# Load_Bank_Mosfet_Control_Board_rev2.net
KiCad netlist of a schematic drawn in EAGLE
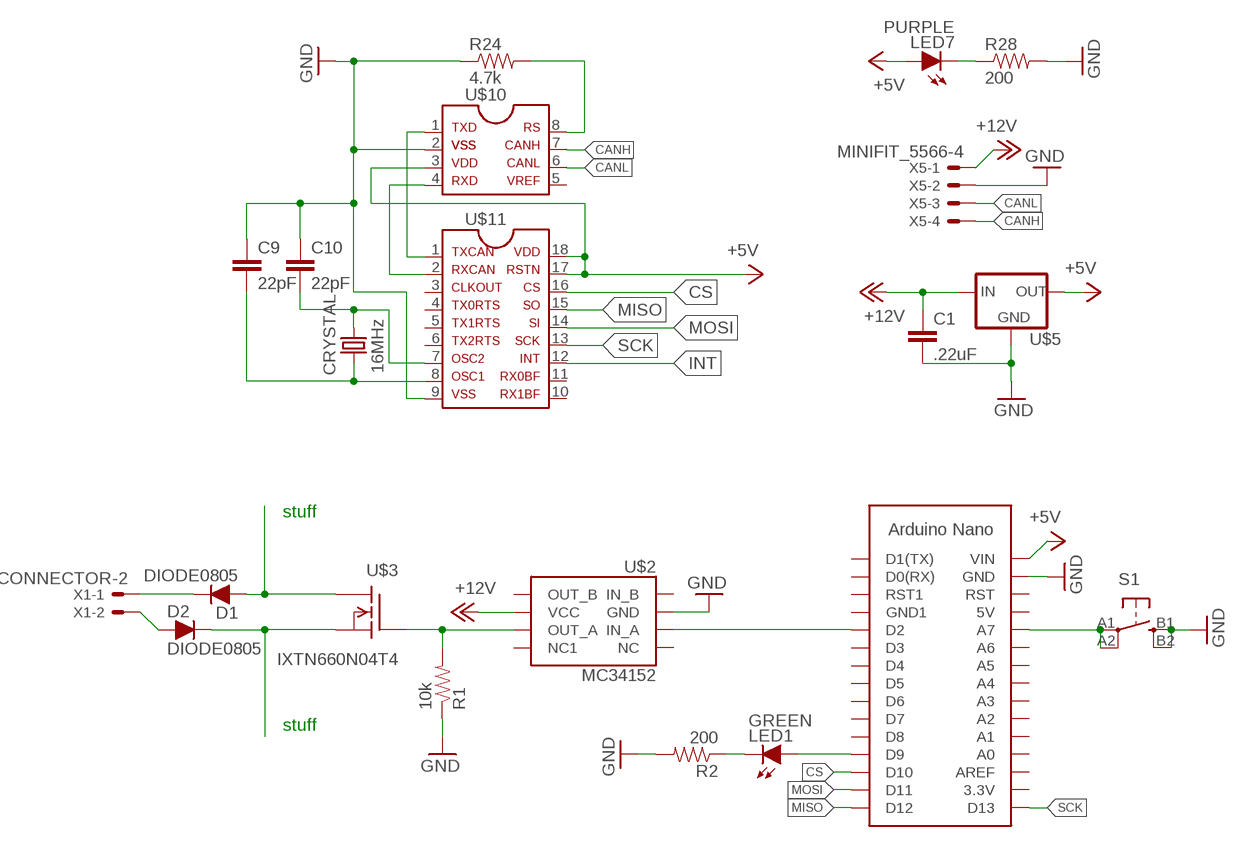
[diagram p0: schematic, sheet 1]

(export (version "E")
  (design (tool "Eeschema 10.0.6"))
  (components
    (comp (ref "C1")
      (value ".22uF")
      (footprint "eagle-import:0805")
      (libsource (lib "eagle-import") (part "CAP0805"))
    )
    (comp (ref "C9")
      (value "22pF")
      (footprint "eagle-import:0805")
      (libsource (lib "eagle-import") (part "CAP0805"))
    )
    (comp (ref "C10")
      (value "22pF")
      (footprint "eagle-import:0805")
      (libsource (lib "eagle-import") (part "CAP0805"))
    )
    (comp (ref "CRYSTAL")
      (value "16MHz")
      (footprint "eagle-import:HC49UP")
      (libsource (lib "eagle-import") (part "CRYSTALSMD"))
    )
    (comp (ref "D1")
      (value "DIODE0805")
      (footprint "eagle-import:0805_D")
      (libsource (lib "eagle-import") (part "DIODE0805"))
    )
    (comp (ref "D2")
      (value "DIODE0805")
      (footprint "eagle-import:0805_D")
      (libsource (lib "eagle-import") (part "DIODE0805"))
    )
    (comp (ref "LED1")
      (value "GREEN")
      (footprint "eagle-import:LED-805")
      (libsource (lib "eagle-import") (part "LED-0805"))
    )
    (comp (ref "LED7")
      (value "PURPLE")
      (footprint "eagle-import:LED-805")
      (libsource (lib "eagle-import") (part "LED-0805"))
    )
    (comp (ref "R1")
      (value "10k")
      (footprint "eagle-import:0805")
      (libsource (lib "eagle-import") (part "HyTechDevices_RESISTOR0805-RES"))
    )
    (comp (ref "R2")
      (value "200")
      (footprint "eagle-import:0805")
      (libsource (lib "eagle-import") (part "HyTechDevices_RESISTOR0805-RES"))
    )
    (comp (ref "R24")
      (value "4.7k")
      (footprint "eagle-import:0805")
      (libsource (lib "eagle-import") (part "HyTechDevices_RESISTOR0805-RES"))
    )
    (comp (ref "R28")
      (value "200")
      (footprint "eagle-import:0805")
      (libsource (lib "eagle-import") (part "HyTechDevices_RESISTOR0805-RES"))
    )
    (comp (ref "S1")
      (value "BTN_10-XXSMD")
      (footprint "eagle-import:TACTILE_SWITCH_SMD_6.2MM_TALL")
      (libsource (lib "eagle-import") (part "BTN_10-XXSMD"))
    )
    (comp (ref "U$2")
      (value "MC34152")
      (footprint "eagle-import:SOIC-08")
      (libsource (lib "eagle-import") (part "MC34152"))
    )
    (comp (ref "U$3")
      (value "IXTN660N04T4")
      (footprint "eagle-import:SOT-227B")
      (libsource (lib "eagle-import") (part "IXTN660N04T4"))
    )
    (comp (ref "U$4")
      (value "ARDUINO_NANO")
      (footprint "eagle-import:ARDUINO_NANO")
      (libsource (lib "eagle-import") (part "ARDUINO_NANO"))
    )
    (comp (ref "U$5")
      (value "5VREG_LM340-NLM340MPX-5.0/NOPB")
      (footprint "eagle-import:SOT223")
      (libsource (lib "eagle-import") (part "5VREG_LM340-NLM340MPX-5.0/NOPB"))
    )
    (comp (ref "U$10")
      (value "MCP2551")
      (footprint "eagle-import:SOIC-08")
      (libsource (lib "eagle-import") (part "MCP2551"))
    )
    (comp (ref "U$11")
      (value "MCP2515SMD")
      (footprint "eagle-import:SOIC-18W")
      (libsource (lib "eagle-import") (part "MCP2515SMD"))
    )
    (comp (ref "X1")
      (value "CONNECTOR-2")
      (footprint "eagle-import:MINIFIT_5566-2")
      (libsource (lib "eagle-import") (part "CONNECTOR-2"))
    )
    (comp (ref "X5")
      (value "MINIFIT_5566-4")
      (footprint "eagle-import:MINIFIT_5566-4")
      (libsource (lib "eagle-import") (part "MINIFIT_5566-4"))
    )
  )
  (nets
    (net (code "1") (name "+5V") (class "Default")
      (node (ref "LED7") (pin "A") (pinfunction "A_A") (pintype "passive"))
      (node (ref "U$10") (pin "3") (pinfunction "3_3") (pintype "passive"))
      (node (ref "U$11") (pin "17") (pinfunction "17_17") (pintype "passive"))
      (node (ref "U$11") (pin "18") (pinfunction "18_18") (pintype "passive"))
      (node (ref "U$4") (pin "VIN") (pinfunction "VIN_VIN") (pintype "bidirectional"))
      (node (ref "U$5") (pin "3") (pinfunction "OUT_3") (pintype "output"))
    )
    (net (code "2") (name "+12V") (class "Default")
      (node (ref "C1") (pin "1") (pinfunction "1_1") (pintype "passive"))
      (node (ref "U$2") (pin "6") (pinfunction "VCC_6") (pintype "power_in"))
      (node (ref "U$5") (pin "1") (pinfunction "IN_1") (pintype "input"))
      (node (ref "X5") (pin "1") (pinfunction "S_1") (pintype "passive"))
    )
    (net (code "3") (name "CANH") (class "Default")
      (node (ref "U$10") (pin "7") (pinfunction "7_7") (pintype "passive"))
      (node (ref "X5") (pin "4") (pinfunction "S_4") (pintype "passive"))
    )
    (net (code "4") (name "CANL") (class "Default")
      (node (ref "U$10") (pin "6") (pinfunction "6_6") (pintype "passive"))
      (node (ref "X5") (pin "3") (pinfunction "S_3") (pintype "passive"))
    )
    (net (code "5") (name "CS") (class "Default")
      (node (ref "U$11") (pin "16") (pinfunction "16_16") (pintype "passive"))
      (node (ref "U$4") (pin "D10") (pinfunction "D10_D10") (pintype "bidirectional"))
    )
    (net (code "6") (name "GND") (class "Default")
      (node (ref "C1") (pin "2") (pinfunction "2_2") (pintype "passive"))
      (node (ref "C10") (pin "1") (pinfunction "1_1") (pintype "passive"))
      (node (ref "C9") (pin "1") (pinfunction "1_1") (pintype "passive"))
      (node (ref "R1") (pin "1") (pinfunction "1_1") (pintype "passive"))
      (node (ref "R2") (pin "2") (pinfunction "2_2") (pintype "passive"))
      (node (ref "R24") (pin "1") (pinfunction "1_1") (pintype "passive"))
      (node (ref "R28") (pin "2") (pinfunction "2_2") (pintype "passive"))
      (node (ref "S1") (pin "B1") (pinfunction "S_B1") (pintype "passive"))
      (node (ref "S1") (pin "B2") (pinfunction "S1_B2") (pintype "passive"))
      (node (ref "U$10") (pin "2") (pinfunction "2_2") (pintype "passive"))
      (node (ref "U$11") (pin "9") (pinfunction "9_9") (pintype "passive"))
      (node (ref "U$2") (pin "3") (pinfunction "GND_3") (pintype "power_in"))
      (node (ref "U$4") (pin "GND") (pinfunction "GND_GND") (pintype "bidirectional"))
      (node (ref "U$5") (pin "2") (pinfunction "GND_2") (pintype "input"))
      (node (ref "U$5") (pin "4") (pinfunction "GND_4") (pintype "input"))
      (node (ref "X5") (pin "2") (pinfunction "S_2") (pintype "passive"))
    )
    (net (code "7") (name "INT") (class "Default")
      (node (ref "U$11") (pin "12") (pinfunction "12_12") (pintype "passive"))
    )
    (net (code "8") (name "MISO") (class "Default")
      (node (ref "U$11") (pin "15") (pinfunction "15_15") (pintype "passive"))
      (node (ref "U$4") (pin "D12") (pinfunction "D12_D12") (pintype "bidirectional"))
    )
    (net (code "9") (name "MOSI") (class "Default")
      (node (ref "U$11") (pin "14") (pinfunction "14_14") (pintype "passive"))
      (node (ref "U$4") (pin "D11") (pinfunction "D11_D11") (pintype "bidirectional"))
    )
    (net (code "10") (name "Net-(C9-Pad2)") (class "Default")
      (node (ref "C9") (pin "2") (pinfunction "2_2") (pintype "passive"))
      (node (ref "CRYSTAL") (pin "2") (pinfunction "2_2") (pintype "passive"))
      (node (ref "U$11") (pin "8") (pinfunction "8_8") (pintype "passive"))
    )
    (net (code "11") (name "Net-(C10-Pad2)") (class "Default")
      (node (ref "C10") (pin "2") (pinfunction "2_2") (pintype "passive"))
      (node (ref "CRYSTAL") (pin "1") (pinfunction "1_1") (pintype "passive"))
      (node (ref "U$11") (pin "7") (pinfunction "7_7") (pintype "passive"))
    )
    (net (code "12") (name "Net-(D2-PadC)") (class "Default")
      (node (ref "D2") (pin "C") (pinfunction "C_C") (pintype "passive"))
      (node (ref "U$3") (pin "P$2") (pinfunction "S_P$2") (pintype "passive"))
      (node (ref "U$3") (pin "P$3") (pinfunction "S_P$3") (pintype "passive"))
    )
    (net (code "13") (name "Net-(LED1-PadA)") (class "Default")
      (node (ref "LED1") (pin "A") (pinfunction "A_A") (pintype "passive"))
      (node (ref "U$4") (pin "D9") (pinfunction "D9_D9") (pintype "bidirectional"))
    )
    (net (code "14") (name "Net-(LED1-PadC)") (class "Default")
      (node (ref "LED1") (pin "C") (pinfunction "C_C") (pintype "passive"))
      (node (ref "R2") (pin "1") (pinfunction "1_1") (pintype "passive"))
    )
    (net (code "15") (name "Net-(LED7-PadC)") (class "Default")
      (node (ref "LED7") (pin "C") (pinfunction "C_C") (pintype "passive"))
      (node (ref "R28") (pin "1") (pinfunction "1_1") (pintype "passive"))
    )
    (net (code "16") (name "Net-(R24-Pad2)") (class "Default")
      (node (ref "R24") (pin "2") (pinfunction "2_2") (pintype "passive"))
      (node (ref "U$10") (pin "8") (pinfunction "8_8") (pintype "passive"))
    )
    (net (code "17") (name "Net-(S1-P)") (class "Default")
      (node (ref "S1") (pin "A1") (pinfunction "P_A1") (pintype "passive"))
      (node (ref "S1") (pin "A2") (pinfunction "P1_A2") (pintype "passive"))
      (node (ref "U$4") (pin "A7") (pinfunction "A7_A7") (pintype "bidirectional"))
    )
    (net (code "18") (name "Net-(U$2-IN_A)") (class "Default")
      (node (ref "U$2") (pin "2") (pinfunction "IN_A_2") (pintype "input"))
      (node (ref "U$4") (pin "D2") (pinfunction "D2_D2") (pintype "bidirectional"))
    )
    (net (code "19") (name "Net-(U$2-OUT_A)") (class "Default")
      (node (ref "R1") (pin "2") (pinfunction "2_2") (pintype "passive"))
      (node (ref "U$2") (pin "7") (pinfunction "OUT_A_7") (pintype "output"))
      (node (ref "U$3") (pin "P$4") (pinfunction "G_P$4") (pintype "passive"))
    )
    (net (code "20") (name "Net-(U$3-D)") (class "Default")
      (node (ref "D1") (pin "A") (pinfunction "A_A") (pintype "passive"))
      (node (ref "U$3") (pin "P$1") (pinfunction "D_P$1") (pintype "passive"))
    )
    (net (code "21") (name "Net-(U$10-Pad1)") (class "Default")
      (node (ref "U$10") (pin "1") (pinfunction "1_1") (pintype "passive"))
      (node (ref "U$11") (pin "1") (pinfunction "1_1") (pintype "passive"))
    )
    (net (code "22") (name "Net-(U$10-Pad4)") (class "Default")
      (node (ref "U$10") (pin "4") (pinfunction "4_4") (pintype "passive"))
      (node (ref "U$11") (pin "2") (pinfunction "2_2") (pintype "passive"))
    )
    (net (code "23") (name "Net-(X1A-S)") (class "Default")
      (node (ref "D1") (pin "C") (pinfunction "C_C") (pintype "passive"))
      (node (ref "X1") (pin "1") (pinfunction "S_1") (pintype "passive"))
    )
    (net (code "24") (name "Net-(X1B-S)") (class "Default")
      (node (ref "D2") (pin "A") (pinfunction "A_A") (pintype "passive"))
      (node (ref "X1") (pin "2") (pinfunction "S_2") (pintype "passive"))
    )
    (net (code "25") (name "SCK") (class "Default")
      (node (ref "U$11") (pin "13") (pinfunction "13_13") (pintype "passive"))
      (node (ref "U$4") (pin "D13") (pinfunction "D13_D13") (pintype "bidirectional"))
    )
    (net (code "26") (name "unconnected-(U$2-IN_B-Pad4)") (class "Default")
      (node (ref "U$2") (pin "4") (pinfunction "IN_B_4") (pintype "bidirectional"))
    )
    (net (code "27") (name "unconnected-(U$2-NC-Pad1)") (class "Default")
      (node (ref "U$2") (pin "1") (pinfunction "NC_1") (pintype "tri_state"))
    )
    (net (code "28") (name "unconnected-(U$2-NC1-Pad8)") (class "Default")
      (node (ref "U$2") (pin "8") (pinfunction "NC1_8") (pintype "tri_state"))
    )
    (net (code "29") (name "unconnected-(U$2-OUT_B-Pad5)") (class "Default")
      (node (ref "U$2") (pin "5") (pinfunction "OUT_B_5") (pintype "output"))
    )
    (net (code "30") (name "unconnected-(U$4-Pad3.3V)") (class "Default")
      (node (ref "U$4") (pin "3.3V") (pinfunction "3.3V_3.3V") (pintype "bidirectional"))
    )
    (net (code "31") (name "unconnected-(U$4-Pad5V)") (class "Default")
      (node (ref "U$4") (pin "5V") (pinfunction "5V_5V") (pintype "bidirectional"))
    )
    (net (code "32") (name "unconnected-(U$4-PadA0)") (class "Default")
      (node (ref "U$4") (pin "A0") (pinfunction "A0_A0") (pintype "bidirectional"))
    )
    (net (code "33") (name "unconnected-(U$4-PadA1)") (class "Default")
      (node (ref "U$4") (pin "A1") (pinfunction "A1_A1") (pintype "bidirectional"))
    )
    (net (code "34") (name "unconnected-(U$4-PadA2)") (class "Default")
      (node (ref "U$4") (pin "A2") (pinfunction "A2_A2") (pintype "bidirectional"))
    )
    (net (code "35") (name "unconnected-(U$4-PadA3)") (class "Default")
      (node (ref "U$4") (pin "A3") (pinfunction "A3_A3") (pintype "bidirectional"))
    )
    (net (code "36") (name "unconnected-(U$4-PadA4)") (class "Default")
      (node (ref "U$4") (pin "A4") (pinfunction "A4_A4") (pintype "bidirectional"))
    )
    (net (code "37") (name "unconnected-(U$4-PadA5)") (class "Default")
      (node (ref "U$4") (pin "A5") (pinfunction "A5_A5") (pintype "bidirectional"))
    )
    (net (code "38") (name "unconnected-(U$4-PadA6)") (class "Default")
      (node (ref "U$4") (pin "A6") (pinfunction "A6_A6") (pintype "bidirectional"))
    )
    (net (code "39") (name "unconnected-(U$4-PadAREF)") (class "Default")
      (node (ref "U$4") (pin "AREF") (pinfunction "AREF_AREF") (pintype "bidirectional"))
    )
    (net (code "40") (name "unconnected-(U$4-PadD0(RX))") (class "Default")
      (node (ref "U$4") (pin "D0(RX)") (pinfunction "D0(RX)_D0(RX)") (pintype "bidirectional"))
    )
    (net (code "41") (name "unconnected-(U$4-PadD1(TX))") (class "Default")
      (node (ref "U$4") (pin "D1(TX)") (pinfunction "D1(TX)_D1(TX)") (pintype "bidirectional"))
    )
    (net (code "42") (name "unconnected-(U$4-PadD3)") (class "Default")
      (node (ref "U$4") (pin "D3") (pinfunction "D3_D3") (pintype "bidirectional"))
    )
    (net (code "43") (name "unconnected-(U$4-PadD4)") (class "Default")
      (node (ref "U$4") (pin "D4") (pinfunction "D4_D4") (pintype "bidirectional"))
    )
    (net (code "44") (name "unconnected-(U$4-PadD5)") (class "Default")
      (node (ref "U$4") (pin "D5") (pinfunction "D5_D5") (pintype "bidirectional"))
    )
    (net (code "45") (name "unconnected-(U$4-PadD6)") (class "Default")
      (node (ref "U$4") (pin "D6") (pinfunction "D6_D6") (pintype "bidirectional"))
    )
    (net (code "46") (name "unconnected-(U$4-PadD7)") (class "Default")
      (node (ref "U$4") (pin "D7") (pinfunction "D7_D7") (pintype "bidirectional"))
    )
    (net (code "47") (name "unconnected-(U$4-PadD8)") (class "Default")
      (node (ref "U$4") (pin "D8") (pinfunction "D8_D8") (pintype "bidirectional"))
    )
    (net (code "48") (name "unconnected-(U$4-PadGND1)") (class "Default")
      (node (ref "U$4") (pin "GND1") (pinfunction "GND1_GND1") (pintype "bidirectional"))
    )
    (net (code "49") (name "unconnected-(U$4-PadRST)") (class "Default")
      (node (ref "U$4") (pin "RST") (pinfunction "RST_RST") (pintype "bidirectional"))
    )
    (net (code "50") (name "unconnected-(U$4-PadRST1)") (class "Default")
      (node (ref "U$4") (pin "RST1") (pinfunction "RST1_RST1") (pintype "bidirectional"))
    )
    (net (code "51") (name "unconnected-(U$10-Pad5)") (class "Default")
      (node (ref "U$10") (pin "5") (pinfunction "5_5") (pintype "passive"))
    )
    (net (code "52") (name "unconnected-(U$11-Pad3)") (class "Default")
      (node (ref "U$11") (pin "3") (pinfunction "3_3") (pintype "passive"))
    )
    (net (code "53") (name "unconnected-(U$11-Pad4)") (class "Default")
      (node (ref "U$11") (pin "4") (pinfunction "4_4") (pintype "passive"))
    )
    (net (code "54") (name "unconnected-(U$11-Pad5)") (class "Default")
      (node (ref "U$11") (pin "5") (pinfunction "5_5") (pintype "passive"))
    )
    (net (code "55") (name "unconnected-(U$11-Pad6)") (class "Default")
      (node (ref "U$11") (pin "6") (pinfunction "6_6") (pintype "passive"))
    )
    (net (code "56") (name "unconnected-(U$11-Pad10)") (class "Default")
      (node (ref "U$11") (pin "10") (pinfunction "10_10") (pintype "passive"))
    )
    (net (code "57") (name "unconnected-(U$11-Pad11)") (class "Default")
      (node (ref "U$11") (pin "11") (pinfunction "11_11") (pintype "passive"))
    )
  )
)
